# main_power.net
KiCad netlist of a schematic drawn in EAGLE
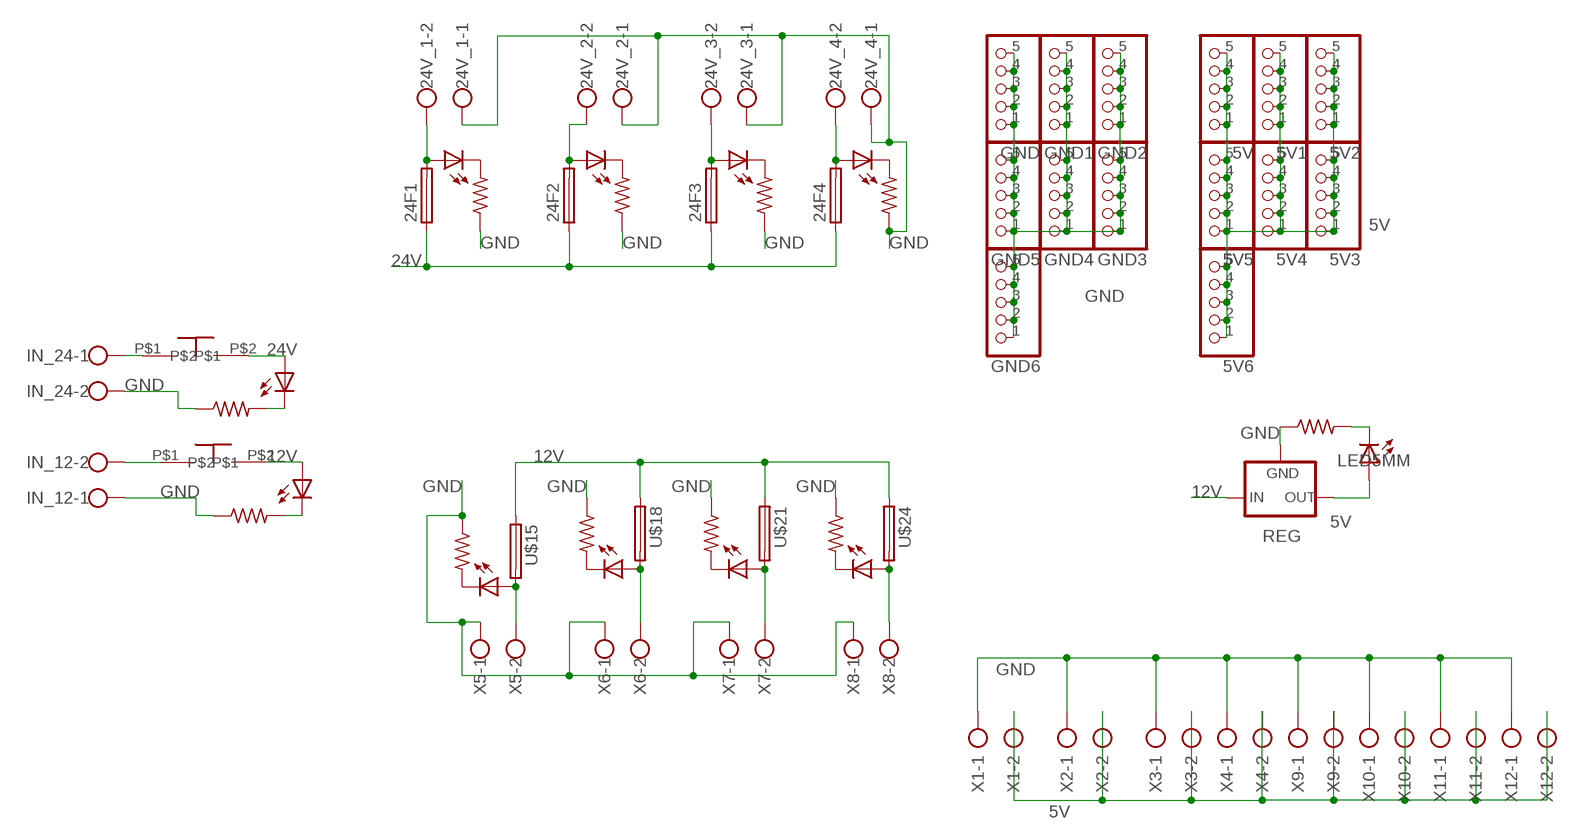
[diagram p0: schematic, sheet 1]

(export (version "E")
  (design (tool "Eeschema 10.0.6"))
  (components
    (comp (ref "5V")
      (value "PINHD-1X5")
      (footprint "eagle-import:1X05")
      (libsource (lib "eagle-import") (part "PINHD-1X5"))
    )
    (comp (ref "5V1")
      (value "PINHD-1X5")
      (footprint "eagle-import:1X05")
      (libsource (lib "eagle-import") (part "PINHD-1X5"))
    )
    (comp (ref "5V2")
      (value "PINHD-1X5")
      (footprint "eagle-import:1X05")
      (libsource (lib "eagle-import") (part "PINHD-1X5"))
    )
    (comp (ref "5V3")
      (value "PINHD-1X5")
      (footprint "eagle-import:1X05")
      (libsource (lib "eagle-import") (part "PINHD-1X5"))
    )
    (comp (ref "5V4")
      (value "PINHD-1X5")
      (footprint "eagle-import:1X05")
      (libsource (lib "eagle-import") (part "PINHD-1X5"))
    )
    (comp (ref "5V5")
      (value "PINHD-1X5")
      (footprint "eagle-import:1X05")
      (libsource (lib "eagle-import") (part "PINHD-1X5"))
    )
    (comp (ref "5V6")
      (value "PINHD-1X5")
      (footprint "eagle-import:1X05")
      (libsource (lib "eagle-import") (part "PINHD-1X5"))
    )
    (comp (ref "12IN")
      (value "RES-7")
      (footprint "eagle-import:0204_7")
      (libsource (lib "eagle-import") (part "RES-7"))
    )
    (comp (ref "12IND")
      (value "LED5MM")
      (footprint "eagle-import:LED5MM")
      (libsource (lib "eagle-import") (part "LED5MM"))
    )
    (comp (ref "24F1")
      (value "FUSE_HOLDER")
      (footprint "eagle-import:SH22,5A")
      (libsource (lib "eagle-import") (part "FUSE_HOLDER"))
    )
    (comp (ref "24F2")
      (value "FUSE_HOLDER")
      (footprint "eagle-import:SH22,5A")
      (libsource (lib "eagle-import") (part "FUSE_HOLDER"))
    )
    (comp (ref "24F3")
      (value "FUSE_HOLDER")
      (footprint "eagle-import:SH22,5A")
      (libsource (lib "eagle-import") (part "FUSE_HOLDER"))
    )
    (comp (ref "24F4")
      (value "FUSE_HOLDER")
      (footprint "eagle-import:SH22,5A")
      (libsource (lib "eagle-import") (part "FUSE_HOLDER"))
    )
    (comp (ref "24V_1")
      (value "ROSTA.POWER")
      (footprint "eagle-import:W239-302")
      (libsource (lib "eagle-import") (part "ROSTA.POWER"))
    )
    (comp (ref "24V_2")
      (value "ROSTA.POWER")
      (footprint "eagle-import:W239-302")
      (libsource (lib "eagle-import") (part "ROSTA.POWER"))
    )
    (comp (ref "24V_3")
      (value "ROSTA.POWER")
      (footprint "eagle-import:W239-302")
      (libsource (lib "eagle-import") (part "ROSTA.POWER"))
    )
    (comp (ref "24V_4")
      (value "ROSTA.POWER")
      (footprint "eagle-import:W239-302")
      (libsource (lib "eagle-import") (part "ROSTA.POWER"))
    )
    (comp (ref "GND")
      (value "PINHD-1X5")
      (footprint "eagle-import:1X05")
      (libsource (lib "eagle-import") (part "PINHD-1X5"))
    )
    (comp (ref "GND1")
      (value "PINHD-1X5")
      (footprint "eagle-import:1X05")
      (libsource (lib "eagle-import") (part "PINHD-1X5"))
    )
    (comp (ref "GND2")
      (value "PINHD-1X5")
      (footprint "eagle-import:1X05")
      (libsource (lib "eagle-import") (part "PINHD-1X5"))
    )
    (comp (ref "GND3")
      (value "PINHD-1X5")
      (footprint "eagle-import:1X05")
      (libsource (lib "eagle-import") (part "PINHD-1X5"))
    )
    (comp (ref "GND4")
      (value "PINHD-1X5")
      (footprint "eagle-import:1X05")
      (libsource (lib "eagle-import") (part "PINHD-1X5"))
    )
    (comp (ref "GND5")
      (value "PINHD-1X5")
      (footprint "eagle-import:1X05")
      (libsource (lib "eagle-import") (part "PINHD-1X5"))
    )
    (comp (ref "GND6")
      (value "PINHD-1X5")
      (footprint "eagle-import:1X05")
      (libsource (lib "eagle-import") (part "PINHD-1X5"))
    )
    (comp (ref "IN24")
      (value "LED5MM")
      (footprint "eagle-import:LED5MM")
      (libsource (lib "eagle-import") (part "LED5MM"))
    )
    (comp (ref "INR24")
      (value "RES-7")
      (footprint "eagle-import:0204_7")
      (libsource (lib "eagle-import") (part "RES-7"))
    )
    (comp (ref "IN_12")
      (value "ROSTA.POWER")
      (footprint "eagle-import:W239-302")
      (libsource (lib "eagle-import") (part "ROSTA.POWER"))
    )
    (comp (ref "IN_24")
      (value "ROSTA.POWER")
      (footprint "eagle-import:W239-302")
      (libsource (lib "eagle-import") (part "ROSTA.POWER"))
    )
    (comp (ref "REG")
      (value "78XX-METAL")
      (footprint "eagle-import:TO3-79")
      (libsource (lib "eagle-import") (part "78XX-METAL"))
    )
    (comp (ref "U$1")
      (value "2k")
      (footprint "eagle-import:0204_7")
      (libsource (lib "eagle-import") (part "RES-7"))
    )
    (comp (ref "U$2")
      (value "LED5MM")
      (footprint "eagle-import:LED5MM")
      (libsource (lib "eagle-import") (part "LED5MM"))
    )
    (comp (ref "U$4")
      (value "LED3MM")
      (footprint "eagle-import:LED3MM")
      (libsource (lib "eagle-import") (part "LED3MM"))
    )
    (comp (ref "U$5")
      (value "RES-7")
      (footprint "eagle-import:0204_7")
      (libsource (lib "eagle-import") (part "RES-7"))
    )
    (comp (ref "U$7")
      (value "LED3MM")
      (footprint "eagle-import:LED3MM")
      (libsource (lib "eagle-import") (part "LED3MM"))
    )
    (comp (ref "U$8")
      (value "RES-7")
      (footprint "eagle-import:0204_7")
      (libsource (lib "eagle-import") (part "RES-7"))
    )
    (comp (ref "U$10")
      (value "LED3MM")
      (footprint "eagle-import:LED3MM")
      (libsource (lib "eagle-import") (part "LED3MM"))
    )
    (comp (ref "U$11")
      (value "RES-7")
      (footprint "eagle-import:0204_7")
      (libsource (lib "eagle-import") (part "RES-7"))
    )
    (comp (ref "U$13")
      (value "LED3MM")
      (footprint "eagle-import:LED3MM")
      (libsource (lib "eagle-import") (part "LED3MM"))
    )
    (comp (ref "U$14")
      (value "RES-7")
      (footprint "eagle-import:0204_7")
      (libsource (lib "eagle-import") (part "RES-7"))
    )
    (comp (ref "U$15")
      (value "FUSE_HOLDER")
      (footprint "eagle-import:SH22,5A")
      (libsource (lib "eagle-import") (part "FUSE_HOLDER"))
    )
    (comp (ref "U$16")
      (value "LED3MM")
      (footprint "eagle-import:LED3MM")
      (libsource (lib "eagle-import") (part "LED3MM"))
    )
    (comp (ref "U$17")
      (value "RES-7")
      (footprint "eagle-import:0204_7")
      (libsource (lib "eagle-import") (part "RES-7"))
    )
    (comp (ref "U$18")
      (value "FUSE_HOLDER")
      (footprint "eagle-import:SH22,5A")
      (libsource (lib "eagle-import") (part "FUSE_HOLDER"))
    )
    (comp (ref "U$19")
      (value "LED3MM")
      (footprint "eagle-import:LED3MM")
      (libsource (lib "eagle-import") (part "LED3MM"))
    )
    (comp (ref "U$20")
      (value "RES-7")
      (footprint "eagle-import:0204_7")
      (libsource (lib "eagle-import") (part "RES-7"))
    )
    (comp (ref "U$21")
      (value "FUSE_HOLDER")
      (footprint "eagle-import:SH22,5A")
      (libsource (lib "eagle-import") (part "FUSE_HOLDER"))
    )
    (comp (ref "U$22")
      (value "LED3MM")
      (footprint "eagle-import:LED3MM")
      (libsource (lib "eagle-import") (part "LED3MM"))
    )
    (comp (ref "U$23")
      (value "RES-7")
      (footprint "eagle-import:0204_7")
      (libsource (lib "eagle-import") (part "RES-7"))
    )
    (comp (ref "U$24")
      (value "FUSE_HOLDER")
      (footprint "eagle-import:SH22,5A")
      (libsource (lib "eagle-import") (part "FUSE_HOLDER"))
    )
    (comp (ref "U$25")
      (value "LED3MM")
      (footprint "eagle-import:LED3MM")
      (libsource (lib "eagle-import") (part "LED3MM"))
    )
    (comp (ref "U$26")
      (value "RES-7")
      (footprint "eagle-import:0204_7")
      (libsource (lib "eagle-import") (part "RES-7"))
    )
    (comp (ref "U$27")
      (value "SWITCH_2")
      (footprint "eagle-import:ON_OFF")
      (libsource (lib "eagle-import") (part "SWITCH_2"))
    )
    (comp (ref "U$28")
      (value "SWITCH_2")
      (footprint "eagle-import:ON_OFF")
      (libsource (lib "eagle-import") (part "SWITCH_2"))
    )
    (comp (ref "X1")
      (value "AK300/22")
      (footprint "eagle-import:XTALRR488W60L1090T465H350B")
      (libsource (lib "eagle-import") (part "AK300/22"))
    )
    (comp (ref "X2")
      (value "AK300/22")
      (footprint "eagle-import:XTALRR488W60L1090T465H350B")
      (libsource (lib "eagle-import") (part "AK300/22"))
    )
    (comp (ref "X3")
      (value "AK300/22")
      (footprint "eagle-import:XTALRR488W60L1090T465H350B")
      (libsource (lib "eagle-import") (part "AK300/22"))
    )
    (comp (ref "X4")
      (value "AK300/22")
      (footprint "eagle-import:XTALRR488W60L1090T465H350B")
      (libsource (lib "eagle-import") (part "AK300/22"))
    )
    (comp (ref "X5")
      (value "ROSTA.POWER")
      (footprint "eagle-import:W239-302")
      (libsource (lib "eagle-import") (part "ROSTA.POWER"))
    )
    (comp (ref "X6")
      (value "ROSTA.POWER")
      (footprint "eagle-import:W239-302")
      (libsource (lib "eagle-import") (part "ROSTA.POWER"))
    )
    (comp (ref "X7")
      (value "ROSTA.POWER")
      (footprint "eagle-import:W239-302")
      (libsource (lib "eagle-import") (part "ROSTA.POWER"))
    )
    (comp (ref "X8")
      (value "ROSTA.POWER")
      (footprint "eagle-import:W239-302")
      (libsource (lib "eagle-import") (part "ROSTA.POWER"))
    )
    (comp (ref "X9")
      (value "AK300/22")
      (footprint "eagle-import:XTALRR488W60L1090T465H350B")
      (libsource (lib "eagle-import") (part "AK300/22"))
    )
    (comp (ref "X10")
      (value "AK300/22")
      (footprint "eagle-import:XTALRR488W60L1090T465H350B")
      (libsource (lib "eagle-import") (part "AK300/22"))
    )
    (comp (ref "X11")
      (value "AK300/22")
      (footprint "eagle-import:XTALRR488W60L1090T465H350B")
      (libsource (lib "eagle-import") (part "AK300/22"))
    )
    (comp (ref "X12")
      (value "AK300/22")
      (footprint "eagle-import:XTALRR488W60L1090T465H350B")
      (libsource (lib "eagle-import") (part "AK300/22"))
    )
  )
  (nets
    (net (code "1") (name "/5V") (class "Default")
      (node (ref "5V") (pin "1") (pinfunction "1_1") (pintype "passive"))
      (node (ref "5V") (pin "2") (pinfunction "2_2") (pintype "passive"))
      (node (ref "5V") (pin "3") (pinfunction "3_3") (pintype "passive"))
      (node (ref "5V") (pin "4") (pinfunction "4_4") (pintype "passive"))
      (node (ref "5V") (pin "5") (pinfunction "5_5") (pintype "passive"))
      (node (ref "5V1") (pin "1") (pinfunction "1_1") (pintype "passive"))
      (node (ref "5V1") (pin "2") (pinfunction "2_2") (pintype "passive"))
      (node (ref "5V1") (pin "3") (pinfunction "3_3") (pintype "passive"))
      (node (ref "5V1") (pin "4") (pinfunction "4_4") (pintype "passive"))
      (node (ref "5V1") (pin "5") (pinfunction "5_5") (pintype "passive"))
      (node (ref "5V2") (pin "1") (pinfunction "1_1") (pintype "passive"))
      (node (ref "5V2") (pin "2") (pinfunction "2_2") (pintype "passive"))
      (node (ref "5V2") (pin "3") (pinfunction "3_3") (pintype "passive"))
      (node (ref "5V2") (pin "4") (pinfunction "4_4") (pintype "passive"))
      (node (ref "5V2") (pin "5") (pinfunction "5_5") (pintype "passive"))
      (node (ref "5V3") (pin "1") (pinfunction "1_1") (pintype "passive"))
      (node (ref "5V3") (pin "2") (pinfunction "2_2") (pintype "passive"))
      (node (ref "5V3") (pin "3") (pinfunction "3_3") (pintype "passive"))
      (node (ref "5V3") (pin "4") (pinfunction "4_4") (pintype "passive"))
      (node (ref "5V3") (pin "5") (pinfunction "5_5") (pintype "passive"))
      (node (ref "5V4") (pin "1") (pinfunction "1_1") (pintype "passive"))
      (node (ref "5V4") (pin "2") (pinfunction "2_2") (pintype "passive"))
      (node (ref "5V4") (pin "3") (pinfunction "3_3") (pintype "passive"))
      (node (ref "5V4") (pin "4") (pinfunction "4_4") (pintype "passive"))
      (node (ref "5V4") (pin "5") (pinfunction "5_5") (pintype "passive"))
      (node (ref "5V5") (pin "1") (pinfunction "1_1") (pintype "passive"))
      (node (ref "5V5") (pin "2") (pinfunction "2_2") (pintype "passive"))
      (node (ref "5V5") (pin "3") (pinfunction "3_3") (pintype "passive"))
      (node (ref "5V5") (pin "4") (pinfunction "4_4") (pintype "passive"))
      (node (ref "5V5") (pin "5") (pinfunction "5_5") (pintype "passive"))
      (node (ref "5V6") (pin "1") (pinfunction "1_1") (pintype "passive"))
      (node (ref "5V6") (pin "2") (pinfunction "2_2") (pintype "passive"))
      (node (ref "5V6") (pin "3") (pinfunction "3_3") (pintype "passive"))
      (node (ref "5V6") (pin "4") (pinfunction "4_4") (pintype "passive"))
      (node (ref "5V6") (pin "5") (pinfunction "5_5") (pintype "passive"))
      (node (ref "REG") (pin "1") (pinfunction "OUT_1") (pintype "passive"))
      (node (ref "U$2") (pin "A") (pinfunction "A_A") (pintype "passive"))
      (node (ref "X1") (pin "2") (pinfunction "KL_2") (pintype "passive"))
      (node (ref "X10") (pin "2") (pinfunction "KL_2") (pintype "passive"))
      (node (ref "X11") (pin "2") (pinfunction "KL_2") (pintype "passive"))
      (node (ref "X12") (pin "2") (pinfunction "KL_2") (pintype "passive"))
      (node (ref "X2") (pin "2") (pinfunction "KL_2") (pintype "passive"))
      (node (ref "X3") (pin "2") (pinfunction "KL_2") (pintype "passive"))
      (node (ref "X4") (pin "2") (pinfunction "KL_2") (pintype "passive"))
      (node (ref "X9") (pin "2") (pinfunction "KL_2") (pintype "passive"))
    )
    (net (code "2") (name "/12V") (class "Default")
      (node (ref "12IND") (pin "A") (pinfunction "A_A") (pintype "passive"))
      (node (ref "REG") (pin "3") (pinfunction "IN_3") (pintype "input"))
      (node (ref "U$15") (pin "1") (pinfunction "1_1") (pintype "passive"))
      (node (ref "U$18") (pin "1") (pinfunction "1_1") (pintype "passive"))
      (node (ref "U$21") (pin "1") (pinfunction "1_1") (pintype "passive"))
      (node (ref "U$24") (pin "1") (pinfunction "1_1") (pintype "passive"))
      (node (ref "U$28") (pin "P$2") (pinfunction "P$2_P$2") (pintype "bidirectional"))
    )
    (net (code "3") (name "/24V") (class "Default")
      (node (ref "24F1") (pin "1") (pinfunction "1_1") (pintype "passive"))
      (node (ref "24F2") (pin "1") (pinfunction "1_1") (pintype "passive"))
      (node (ref "24F3") (pin "1") (pinfunction "1_1") (pintype "passive"))
      (node (ref "24F4") (pin "1") (pinfunction "1_1") (pintype "passive"))
      (node (ref "IN24") (pin "A") (pinfunction "A_A") (pintype "passive"))
      (node (ref "U$27") (pin "P$2") (pinfunction "P$2_P$2") (pintype "bidirectional"))
    )
    (net (code "4") (name "/GND") (class "Default")
      (node (ref "12IN") (pin "1") (pinfunction "1_1") (pintype "passive"))
      (node (ref "24V_1") (pin "1") (pinfunction "KL_1") (pintype "passive"))
      (node (ref "24V_2") (pin "1") (pinfunction "KL_1") (pintype "passive"))
      (node (ref "24V_3") (pin "1") (pinfunction "KL_1") (pintype "passive"))
      (node (ref "24V_4") (pin "1") (pinfunction "KL_1") (pintype "passive"))
      (node (ref "GND") (pin "1") (pinfunction "1_1") (pintype "passive"))
      (node (ref "GND") (pin "2") (pinfunction "2_2") (pintype "passive"))
      (node (ref "GND") (pin "3") (pinfunction "3_3") (pintype "passive"))
      (node (ref "GND") (pin "4") (pinfunction "4_4") (pintype "passive"))
      (node (ref "GND") (pin "5") (pinfunction "5_5") (pintype "passive"))
      (node (ref "GND1") (pin "1") (pinfunction "1_1") (pintype "passive"))
      (node (ref "GND1") (pin "2") (pinfunction "2_2") (pintype "passive"))
      (node (ref "GND1") (pin "3") (pinfunction "3_3") (pintype "passive"))
      (node (ref "GND1") (pin "4") (pinfunction "4_4") (pintype "passive"))
      (node (ref "GND1") (pin "5") (pinfunction "5_5") (pintype "passive"))
      (node (ref "GND2") (pin "1") (pinfunction "1_1") (pintype "passive"))
      (node (ref "GND2") (pin "2") (pinfunction "2_2") (pintype "passive"))
      (node (ref "GND2") (pin "3") (pinfunction "3_3") (pintype "passive"))
      (node (ref "GND2") (pin "4") (pinfunction "4_4") (pintype "passive"))
      (node (ref "GND2") (pin "5") (pinfunction "5_5") (pintype "passive"))
      (node (ref "GND3") (pin "1") (pinfunction "1_1") (pintype "passive"))
      (node (ref "GND3") (pin "2") (pinfunction "2_2") (pintype "passive"))
      (node (ref "GND3") (pin "3") (pinfunction "3_3") (pintype "passive"))
      (node (ref "GND3") (pin "4") (pinfunction "4_4") (pintype "passive"))
      (node (ref "GND3") (pin "5") (pinfunction "5_5") (pintype "passive"))
      (node (ref "GND4") (pin "1") (pinfunction "1_1") (pintype "passive"))
      (node (ref "GND4") (pin "2") (pinfunction "2_2") (pintype "passive"))
      (node (ref "GND4") (pin "3") (pinfunction "3_3") (pintype "passive"))
      (node (ref "GND4") (pin "4") (pinfunction "4_4") (pintype "passive"))
      (node (ref "GND4") (pin "5") (pinfunction "5_5") (pintype "passive"))
      (node (ref "GND5") (pin "1") (pinfunction "1_1") (pintype "passive"))
      (node (ref "GND5") (pin "2") (pinfunction "2_2") (pintype "passive"))
      (node (ref "GND5") (pin "3") (pinfunction "3_3") (pintype "passive"))
      (node (ref "GND5") (pin "4") (pinfunction "4_4") (pintype "passive"))
      (node (ref "GND5") (pin "5") (pinfunction "5_5") (pintype "passive"))
      (node (ref "GND6") (pin "1") (pinfunction "1_1") (pintype "passive"))
      (node (ref "GND6") (pin "2") (pinfunction "2_2") (pintype "passive"))
      (node (ref "GND6") (pin "3") (pinfunction "3_3") (pintype "passive"))
      (node (ref "GND6") (pin "4") (pinfunction "4_4") (pintype "passive"))
      (node (ref "GND6") (pin "5") (pinfunction "5_5") (pintype "passive"))
      (node (ref "INR24") (pin "1") (pinfunction "1_1") (pintype "passive"))
      (node (ref "IN_12") (pin "1") (pinfunction "KL_1") (pintype "passive"))
      (node (ref "IN_24") (pin "2") (pinfunction "KL_2") (pintype "passive"))
      (node (ref "REG") (pin "2") (pinfunction "GND_2") (pintype "input"))
      (node (ref "U$1") (pin "1") (pinfunction "1_1") (pintype "passive"))
      (node (ref "U$11") (pin "1") (pinfunction "1_1") (pintype "passive"))
      (node (ref "U$14") (pin "1") (pinfunction "1_1") (pintype "passive"))
      (node (ref "U$17") (pin "1") (pinfunction "1_1") (pintype "passive"))
      (node (ref "U$20") (pin "1") (pinfunction "1_1") (pintype "passive"))
      (node (ref "U$23") (pin "1") (pinfunction "1_1") (pintype "passive"))
      (node (ref "U$26") (pin "1") (pinfunction "1_1") (pintype "passive"))
      (node (ref "U$5") (pin "1") (pinfunction "1_1") (pintype "passive"))
      (node (ref "U$8") (pin "1") (pinfunction "1_1") (pintype "passive"))
      (node (ref "X1") (pin "1") (pinfunction "KL_1") (pintype "passive"))
      (node (ref "X10") (pin "1") (pinfunction "KL_1") (pintype "passive"))
      (node (ref "X11") (pin "1") (pinfunction "KL_1") (pintype "passive"))
      (node (ref "X12") (pin "1") (pinfunction "KL_1") (pintype "passive"))
      (node (ref "X2") (pin "1") (pinfunction "KL_1") (pintype "passive"))
      (node (ref "X3") (pin "1") (pinfunction "KL_1") (pintype "passive"))
      (node (ref "X4") (pin "1") (pinfunction "KL_1") (pintype "passive"))
      (node (ref "X5") (pin "1") (pinfunction "KL_1") (pintype "passive"))
      (node (ref "X6") (pin "1") (pinfunction "KL_1") (pintype "passive"))
      (node (ref "X7") (pin "1") (pinfunction "KL_1") (pintype "passive"))
      (node (ref "X8") (pin "1") (pinfunction "KL_1") (pintype "passive"))
      (node (ref "X9") (pin "1") (pinfunction "KL_1") (pintype "passive"))
    )
    (net (code "5") (name "Net-(12IND-C)") (class "Default")
      (node (ref "12IN") (pin "2") (pinfunction "2_2") (pintype "passive"))
      (node (ref "12IND") (pin "K") (pinfunction "C_K") (pintype "passive"))
    )
    (net (code "6") (name "Net-(24V_1B-KL)") (class "Default")
      (node (ref "24F1") (pin "2") (pinfunction "2_2") (pintype "passive"))
      (node (ref "24V_1") (pin "2") (pinfunction "KL_2") (pintype "passive"))
      (node (ref "U$4") (pin "A") (pinfunction "A_A") (pintype "passive"))
    )
    (net (code "7") (name "Net-(24V_2B-KL)") (class "Default")
      (node (ref "24F2") (pin "2") (pinfunction "2_2") (pintype "passive"))
      (node (ref "24V_2") (pin "2") (pinfunction "KL_2") (pintype "passive"))
      (node (ref "U$7") (pin "A") (pinfunction "A_A") (pintype "passive"))
    )
    (net (code "8") (name "Net-(24V_3B-KL)") (class "Default")
      (node (ref "24F3") (pin "2") (pinfunction "2_2") (pintype "passive"))
      (node (ref "24V_3") (pin "2") (pinfunction "KL_2") (pintype "passive"))
      (node (ref "U$10") (pin "A") (pinfunction "A_A") (pintype "passive"))
    )
    (net (code "9") (name "Net-(24V_4B-KL)") (class "Default")
      (node (ref "24F4") (pin "2") (pinfunction "2_2") (pintype "passive"))
      (node (ref "24V_4") (pin "2") (pinfunction "KL_2") (pintype "passive"))
      (node (ref "U$13") (pin "A") (pinfunction "A_A") (pintype "passive"))
    )
    (net (code "10") (name "Net-(IN24-C)") (class "Default")
      (node (ref "IN24") (pin "K") (pinfunction "C_K") (pintype "passive"))
      (node (ref "INR24") (pin "2") (pinfunction "2_2") (pintype "passive"))
    )
    (net (code "11") (name "Net-(IN_12B-KL)") (class "Default")
      (node (ref "IN_12") (pin "2") (pinfunction "KL_2") (pintype "passive"))
      (node (ref "U$28") (pin "P$1") (pinfunction "P$1_P$1") (pintype "bidirectional"))
    )
    (net (code "12") (name "Net-(IN_24A-KL)") (class "Default")
      (node (ref "IN_24") (pin "1") (pinfunction "KL_1") (pintype "passive"))
      (node (ref "U$27") (pin "P$1") (pinfunction "P$1_P$1") (pintype "bidirectional"))
    )
    (net (code "13") (name "Net-(U$2-C)") (class "Default")
      (node (ref "U$1") (pin "2") (pinfunction "2_2") (pintype "passive"))
      (node (ref "U$2") (pin "K") (pinfunction "C_K") (pintype "passive"))
    )
    (net (code "14") (name "Net-(U$4-C)") (class "Default")
      (node (ref "U$4") (pin "K") (pinfunction "C_K") (pintype "passive"))
      (node (ref "U$5") (pin "2") (pinfunction "2_2") (pintype "passive"))
    )
    (net (code "15") (name "Net-(U$7-C)") (class "Default")
      (node (ref "U$7") (pin "K") (pinfunction "C_K") (pintype "passive"))
      (node (ref "U$8") (pin "2") (pinfunction "2_2") (pintype "passive"))
    )
    (net (code "16") (name "Net-(U$10-C)") (class "Default")
      (node (ref "U$10") (pin "K") (pinfunction "C_K") (pintype "passive"))
      (node (ref "U$11") (pin "2") (pinfunction "2_2") (pintype "passive"))
    )
    (net (code "17") (name "Net-(U$13-C)") (class "Default")
      (node (ref "U$13") (pin "K") (pinfunction "C_K") (pintype "passive"))
      (node (ref "U$14") (pin "2") (pinfunction "2_2") (pintype "passive"))
    )
    (net (code "18") (name "Net-(U$16-C)") (class "Default")
      (node (ref "U$16") (pin "K") (pinfunction "C_K") (pintype "passive"))
      (node (ref "U$17") (pin "2") (pinfunction "2_2") (pintype "passive"))
    )
    (net (code "19") (name "Net-(U$19-C)") (class "Default")
      (node (ref "U$19") (pin "K") (pinfunction "C_K") (pintype "passive"))
      (node (ref "U$20") (pin "2") (pinfunction "2_2") (pintype "passive"))
    )
    (net (code "20") (name "Net-(U$22-C)") (class "Default")
      (node (ref "U$22") (pin "K") (pinfunction "C_K") (pintype "passive"))
      (node (ref "U$23") (pin "2") (pinfunction "2_2") (pintype "passive"))
    )
    (net (code "21") (name "Net-(U$25-C)") (class "Default")
      (node (ref "U$25") (pin "K") (pinfunction "C_K") (pintype "passive"))
      (node (ref "U$26") (pin "2") (pinfunction "2_2") (pintype "passive"))
    )
    (net (code "22") (name "Net-(X5B-KL)") (class "Default")
      (node (ref "U$15") (pin "2") (pinfunction "2_2") (pintype "passive"))
      (node (ref "U$16") (pin "A") (pinfunction "A_A") (pintype "passive"))
      (node (ref "X5") (pin "2") (pinfunction "KL_2") (pintype "passive"))
    )
    (net (code "23") (name "Net-(X6B-KL)") (class "Default")
      (node (ref "U$18") (pin "2") (pinfunction "2_2") (pintype "passive"))
      (node (ref "U$19") (pin "A") (pinfunction "A_A") (pintype "passive"))
      (node (ref "X6") (pin "2") (pinfunction "KL_2") (pintype "passive"))
    )
    (net (code "24") (name "Net-(X7B-KL)") (class "Default")
      (node (ref "U$21") (pin "2") (pinfunction "2_2") (pintype "passive"))
      (node (ref "U$22") (pin "A") (pinfunction "A_A") (pintype "passive"))
      (node (ref "X7") (pin "2") (pinfunction "KL_2") (pintype "passive"))
    )
    (net (code "25") (name "Net-(X8B-KL)") (class "Default")
      (node (ref "U$24") (pin "2") (pinfunction "2_2") (pintype "passive"))
      (node (ref "U$25") (pin "A") (pinfunction "A_A") (pintype "passive"))
      (node (ref "X8") (pin "2") (pinfunction "KL_2") (pintype "passive"))
    )
  )
)
